# v2.net
KiCad netlist of a schematic drawn in EAGLE
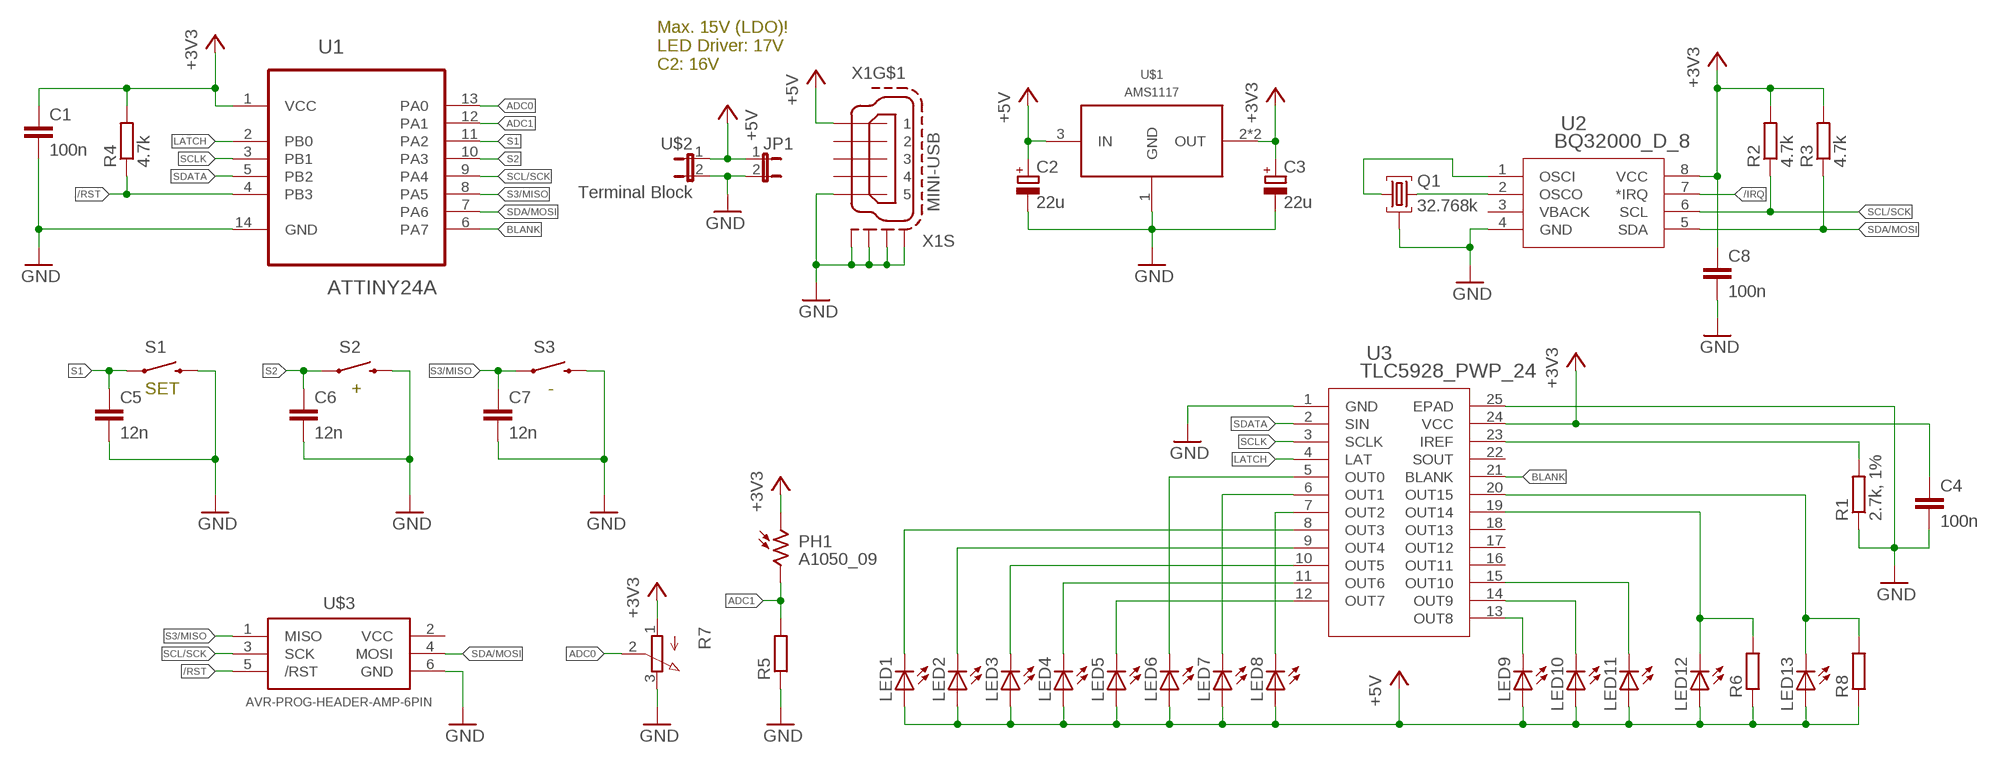
[diagram p0: schematic, sheet 1]
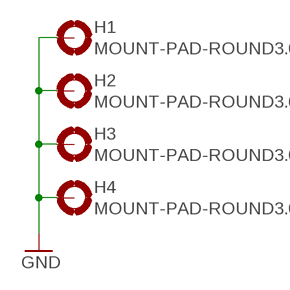
[diagram p1: schematic, sheet 2]

(export (version "E")
  (design (tool "Eeschema 10.0.6"))
  (components
    (comp (ref "H1")
      (value "MOUNT-PAD-ROUND3.0")
      (footprint "eagle-import:3,0-PAD")
      (libsource (lib "eagle-import") (part "MOUNT-PAD-ROUND3.0"))
    )
    (comp (ref "H2")
      (value "MOUNT-PAD-ROUND3.0")
      (footprint "eagle-import:3,0-PAD")
      (libsource (lib "eagle-import") (part "MOUNT-PAD-ROUND3.0"))
    )
    (comp (ref "H3")
      (value "MOUNT-PAD-ROUND3.0")
      (footprint "eagle-import:3,0-PAD")
      (libsource (lib "eagle-import") (part "MOUNT-PAD-ROUND3.0"))
    )
    (comp (ref "H4")
      (value "MOUNT-PAD-ROUND3.0")
      (footprint "eagle-import:3,0-PAD")
      (libsource (lib "eagle-import") (part "MOUNT-PAD-ROUND3.0"))
    )
    (comp (ref "C1")
      (value "100n")
      (footprint "eagle-import:C0603")
      (libsource (lib "eagle-import") (part "C-EUC0603"))
    )
    (comp (ref "C2")
      (value "22u")
      (footprint "eagle-import:153CLV-0505")
      (libsource (lib "eagle-import") (part "CPOL-EU153CLV-0505"))
    )
    (comp (ref "C3")
      (value "22u")
      (footprint "eagle-import:153CLV-0505")
      (libsource (lib "eagle-import") (part "CPOL-EU153CLV-0505"))
    )
    (comp (ref "C4")
      (value "100n")
      (footprint "eagle-import:C0603")
      (libsource (lib "eagle-import") (part "C-EUC0603"))
    )
    (comp (ref "C5")
      (value "12n")
      (footprint "eagle-import:C0603")
      (libsource (lib "eagle-import") (part "C-EUC0603"))
    )
    (comp (ref "C6")
      (value "12n")
      (footprint "eagle-import:C0603")
      (libsource (lib "eagle-import") (part "C-EUC0603"))
    )
    (comp (ref "C7")
      (value "12n")
      (footprint "eagle-import:C0603")
      (libsource (lib "eagle-import") (part "C-EUC0603"))
    )
    (comp (ref "C8")
      (value "100n")
      (footprint "eagle-import:C0603")
      (libsource (lib "eagle-import") (part "C-EUC0603"))
    )
    (comp (ref "JP1")
      (value "JP1E")
      (footprint "eagle-import:JP1")
      (libsource (lib "eagle-import") (part "JP1E"))
    )
    (comp (ref "LED1")
      (value "LEDCHIP-LED0603")
      (footprint "eagle-import:CHIP-LED0603")
      (libsource (lib "eagle-import") (part "LEDCHIP-LED0603"))
    )
    (comp (ref "LED2")
      (value "LEDCHIP-LED0603")
      (footprint "eagle-import:CHIP-LED0603")
      (libsource (lib "eagle-import") (part "LEDCHIP-LED0603"))
    )
    (comp (ref "LED3")
      (value "LEDCHIP-LED0603")
      (footprint "eagle-import:CHIP-LED0603")
      (libsource (lib "eagle-import") (part "LEDCHIP-LED0603"))
    )
    (comp (ref "LED4")
      (value "LEDCHIP-LED0603")
      (footprint "eagle-import:CHIP-LED0603")
      (libsource (lib "eagle-import") (part "LEDCHIP-LED0603"))
    )
    (comp (ref "LED5")
      (value "LEDCHIP-LED0603")
      (footprint "eagle-import:CHIP-LED0603")
      (libsource (lib "eagle-import") (part "LEDCHIP-LED0603"))
    )
    (comp (ref "LED6")
      (value "LEDCHIP-LED0603")
      (footprint "eagle-import:CHIP-LED0603")
      (libsource (lib "eagle-import") (part "LEDCHIP-LED0603"))
    )
    (comp (ref "LED7")
      (value "LEDCHIP-LED0603")
      (footprint "eagle-import:CHIP-LED0603")
      (libsource (lib "eagle-import") (part "LEDCHIP-LED0603"))
    )
    (comp (ref "LED8")
      (value "LEDCHIP-LED0603")
      (footprint "eagle-import:CHIP-LED0603")
      (libsource (lib "eagle-import") (part "LEDCHIP-LED0603"))
    )
    (comp (ref "LED9")
      (value "LEDCHIP-LED0603")
      (footprint "eagle-import:CHIP-LED0603")
      (libsource (lib "eagle-import") (part "LEDCHIP-LED0603"))
    )
    (comp (ref "LED10")
      (value "LEDCHIP-LED0603")
      (footprint "eagle-import:CHIP-LED0603")
      (libsource (lib "eagle-import") (part "LEDCHIP-LED0603"))
    )
    (comp (ref "LED11")
      (value "LEDCHIP-LED0603")
      (footprint "eagle-import:CHIP-LED0603")
      (libsource (lib "eagle-import") (part "LEDCHIP-LED0603"))
    )
    (comp (ref "LED12")
      (value "LEDCHIP-LED0603")
      (footprint "eagle-import:CHIP-LED0603")
      (libsource (lib "eagle-import") (part "LEDCHIP-LED0603"))
    )
    (comp (ref "LED13")
      (value "LEDCHIP-LED0603")
      (footprint "eagle-import:CHIP-LED0603")
      (libsource (lib "eagle-import") (part "LEDCHIP-LED0603"))
    )
    (comp (ref "PH1")
      (value "A1050_09")
      (footprint "eagle-import:T0-46-A10XX")
      (libsource (lib "eagle-import") (part "A1050_09"))
    )
    (comp (ref "Q1")
      (value "32.768k")
      (footprint "eagle-import:TC38")
      (libsource (lib "eagle-import") (part "CRYSTAL_TC38_SHIELD"))
    )
    (comp (ref "R1")
      (value "2.7k, 1%")
      (footprint "eagle-import:R1206")
      (libsource (lib "eagle-import") (part "R-EU_R1206"))
    )
    (comp (ref "R2")
      (value "4.7k")
      (footprint "eagle-import:R0603")
      (libsource (lib "eagle-import") (part "R-EU_R0603"))
    )
    (comp (ref "R3")
      (value "4.7k")
      (footprint "eagle-import:R0603")
      (libsource (lib "eagle-import") (part "R-EU_R0603"))
    )
    (comp (ref "R4")
      (value "4.7k")
      (footprint "eagle-import:R0603")
      (libsource (lib "eagle-import") (part "R-EU_R0603"))
    )
    (comp (ref "R5")
      (value "R-EU_R0603")
      (footprint "eagle-import:R0603")
      (libsource (lib "eagle-import") (part "R-EU_R0603"))
    )
    (comp (ref "R6")
      (value "R-EU_R0603")
      (footprint "eagle-import:R0603")
      (libsource (lib "eagle-import") (part "R-EU_R0603"))
    )
    (comp (ref "R7")
      (value "3RP/1610N")
      (footprint "eagle-import:3RP_1610N")
      (libsource (lib "eagle-import") (part "3RP/1610N"))
    )
    (comp (ref "R8")
      (value "R-EU_R0603")
      (footprint "eagle-import:R0603")
      (libsource (lib "eagle-import") (part "R-EU_R0603"))
    )
    (comp (ref "S1")
      (value "SWITCH-MOMENTARY-2PTH")
      (footprint "eagle-import:TACTILE-PTH")
      (libsource (lib "eagle-import") (part "SWITCH-MOMENTARY-2PTH"))
    )
    (comp (ref "S2")
      (value "SWITCH-MOMENTARY-2PTH")
      (footprint "eagle-import:TACTILE-PTH")
      (libsource (lib "eagle-import") (part "SWITCH-MOMENTARY-2PTH"))
    )
    (comp (ref "S3")
      (value "SWITCH-MOMENTARY-2PTH")
      (footprint "eagle-import:TACTILE-PTH")
      (libsource (lib "eagle-import") (part "SWITCH-MOMENTARY-2PTH"))
    )
    (comp (ref "U$1")
      (value "AMS1117")
      (footprint "eagle-import:DCY4")
      (libsource (lib "eagle-import") (part "AMS1117"))
    )
    (comp (ref "U$2")
      (value "Terminal Block")
      (footprint "eagle-import:BASTLI_SCREW_TERMINAL_SMALL")
      (libsource (lib "eagle-import") (part "BASTLI_SCREW_TERMINAL_SMALL"))
    )
    (comp (ref "U$3")
      (value "AVR-PROG-HEADER-AMP-6PIN")
      (footprint "eagle-import:AMP-TMM-1-0-06")
      (libsource (lib "eagle-import") (part "AVR-PROG-HEADER-AMP-6PIN"))
    )
    (comp (ref "U1")
      (value "ATTINY24A")
      (footprint "eagle-import:SOIC127P600X175-14N")
      (fields (field (name "MPN") "ATTINY24A-SSU"))
      (libsource (lib "eagle-import") (part "ATTINY24A-SSU"))
    )
    (comp (ref "U2")
      (value "BQ32000_D_8")
      (footprint "eagle-import:D8")
      (fields
        (field (name "GENERIC_PART_NUMBER") "BQ32000")
        (field (name "MANUFACTURER") "Texas Instruments")
      )
      (libsource (lib "eagle-import") (part "BQ32000_D_8"))
    )
    (comp (ref "U3")
      (value "TLC5928_PWP_24")
      (footprint "eagle-import:PWP24_4P87X2P4")
      (fields
        (field (name "GENERIC_PART_NUMBER") "TLC5928")
        (field (name "MANUFACTURER") "Texas Instruments")
        (field (name "MANUFACTURER_PART_NUMBER") "tlc5928_pwp_24")
      )
      (libsource (lib "eagle-import") (part "TLC5928_PWP_24"))
    )
    (comp (ref "X1")
      (value "MINI-USB")
      (footprint "eagle-import:32005-201")
      (libsource (lib "eagle-import") (part "MINI-USB-SCHIELD-32005-201"))
    )
  )
  (nets
    (net (code "1") (name "+3V3") (class "Default")
      (node (ref "C1") (pin "1") (pinfunction "1_1") (pintype "passive"))
      (node (ref "C3") (pin "+") (pinfunction "+_+") (pintype "passive"))
      (node (ref "C4") (pin "1") (pinfunction "1_1") (pintype "passive"))
      (node (ref "C8") (pin "1") (pinfunction "1_1") (pintype "passive"))
      (node (ref "PH1") (pin "1") (pinfunction "1_1") (pintype "passive"))
      (node (ref "R2") (pin "2") (pinfunction "2_2") (pintype "passive"))
      (node (ref "R3") (pin "2") (pinfunction "2_2") (pintype "passive"))
      (node (ref "R4") (pin "2") (pinfunction "2_2") (pintype "passive"))
      (node (ref "R7") (pin "1") (pinfunction "A_1") (pintype "passive"))
      (node (ref "U$1") (pin "2") (pinfunction "OUT_2") (pintype "power_in"))
      (node (ref "U$1") (pin "4") (pinfunction "OUT_4") (pintype "power_in"))
      (node (ref "U1") (pin "1") (pinfunction "VCC_1") (pintype "power_in"))
      (node (ref "U2") (pin "8") (pinfunction "VCC_8") (pintype "power_in"))
      (node (ref "U3") (pin "24") (pinfunction "VCC_24") (pintype "power_in"))
    )
    (net (code "2") (name "+5V") (class "Default")
      (node (ref "C2") (pin "+") (pinfunction "+_+") (pintype "passive"))
      (node (ref "JP1") (pin "1") (pinfunction "1_1") (pintype "passive"))
      (node (ref "LED1") (pin "A") (pinfunction "A_A") (pintype "passive"))
      (node (ref "LED10") (pin "A") (pinfunction "A_A") (pintype "passive"))
      (node (ref "LED11") (pin "A") (pinfunction "A_A") (pintype "passive"))
      (node (ref "LED12") (pin "A") (pinfunction "A_A") (pintype "passive"))
      (node (ref "LED13") (pin "A") (pinfunction "A_A") (pintype "passive"))
      (node (ref "LED2") (pin "A") (pinfunction "A_A") (pintype "passive"))
      (node (ref "LED3") (pin "A") (pinfunction "A_A") (pintype "passive"))
      (node (ref "LED4") (pin "A") (pinfunction "A_A") (pintype "passive"))
      (node (ref "LED5") (pin "A") (pinfunction "A_A") (pintype "passive"))
      (node (ref "LED6") (pin "A") (pinfunction "A_A") (pintype "passive"))
      (node (ref "LED7") (pin "A") (pinfunction "A_A") (pintype "passive"))
      (node (ref "LED8") (pin "A") (pinfunction "A_A") (pintype "passive"))
      (node (ref "LED9") (pin "A") (pinfunction "A_A") (pintype "passive"))
      (node (ref "R6") (pin "1") (pinfunction "1_1") (pintype "passive"))
      (node (ref "R8") (pin "1") (pinfunction "1_1") (pintype "passive"))
      (node (ref "U$1") (pin "3") (pinfunction "IN_3") (pintype "power_in"))
      (node (ref "U$2") (pin "1") (pinfunction "1_1") (pintype "passive"))
      (node (ref "X1") (pin "1") (pinfunction "1_1") (pintype "passive"))
    )
    (net (code "3") (name "ADC0") (class "Default")
      (node (ref "R7") (pin "2") (pinfunction "S_2") (pintype "passive"))
      (node (ref "U1") (pin "13") (pinfunction "PA0_13") (pintype "bidirectional"))
    )
    (net (code "4") (name "ADC1") (class "Default")
      (node (ref "PH1") (pin "2") (pinfunction "2_2") (pintype "passive"))
      (node (ref "R5") (pin "2") (pinfunction "2_2") (pintype "passive"))
      (node (ref "U1") (pin "12") (pinfunction "PA1_12") (pintype "bidirectional"))
    )
    (net (code "5") (name "BLANK") (class "Default")
      (node (ref "U1") (pin "6") (pinfunction "PA7_6") (pintype "bidirectional"))
      (node (ref "U3") (pin "21") (pinfunction "BLANK_21") (pintype "input"))
    )
    (net (code "6") (name "GND") (class "Default")
      (node (ref "C1") (pin "2") (pinfunction "2_2") (pintype "passive"))
      (node (ref "C2") (pin "-") (pinfunction "-_-") (pintype "passive"))
      (node (ref "C3") (pin "-") (pinfunction "-_-") (pintype "passive"))
      (node (ref "C4") (pin "2") (pinfunction "2_2") (pintype "passive"))
      (node (ref "C5") (pin "2") (pinfunction "2_2") (pintype "passive"))
      (node (ref "C6") (pin "2") (pinfunction "2_2") (pintype "passive"))
      (node (ref "C7") (pin "2") (pinfunction "2_2") (pintype "passive"))
      (node (ref "C8") (pin "2") (pinfunction "2_2") (pintype "passive"))
      (node (ref "H1") (pin "B3,0") (pinfunction "MOUNT_B3,0") (pintype "passive"))
      (node (ref "H2") (pin "B3,0") (pinfunction "MOUNT_B3,0") (pintype "passive"))
      (node (ref "H3") (pin "B3,0") (pinfunction "MOUNT_B3,0") (pintype "passive"))
      (node (ref "H4") (pin "B3,0") (pinfunction "MOUNT_B3,0") (pintype "passive"))
      (node (ref "JP1") (pin "2") (pinfunction "2_2") (pintype "passive"))
      (node (ref "Q1") (pin "1") (pinfunction "2_1") (pintype "passive"))
      (node (ref "R1") (pin "1") (pinfunction "1_1") (pintype "passive"))
      (node (ref "R5") (pin "1") (pinfunction "1_1") (pintype "passive"))
      (node (ref "R7") (pin "3") (pinfunction "E_3") (pintype "passive"))
      (node (ref "S1") (pin "3") (pinfunction "2_3") (pintype "passive"))
      (node (ref "S2") (pin "3") (pinfunction "2_3") (pintype "passive"))
      (node (ref "S3") (pin "3") (pinfunction "2_3") (pintype "passive"))
      (node (ref "U$1") (pin "1") (pinfunction "GND_1") (pintype "input"))
      (node (ref "U$2") (pin "2") (pinfunction "2_2") (pintype "passive"))
      (node (ref "U$3") (pin "6") (pinfunction "GND_6") (pintype "bidirectional"))
      (node (ref "U1") (pin "14") (pinfunction "GND_14") (pintype "power_in"))
      (node (ref "U2") (pin "4") (pinfunction "GND_4") (pintype "power_in"))
      (node (ref "U3") (pin "1") (pinfunction "GND_1") (pintype "power_in"))
      (node (ref "U3") (pin "25") (pinfunction "EPAD_25") (pintype "passive"))
      (node (ref "X1") (pin "5") (pinfunction "5_5") (pintype "passive"))
      (node (ref "X1") (pin "M1") (pinfunction "S1_M1") (pintype "passive"))
      (node (ref "X1") (pin "M2") (pinfunction "S2_M2") (pintype "passive"))
      (node (ref "X1") (pin "M3") (pinfunction "S3_M3") (pintype "passive"))
      (node (ref "X1") (pin "M4") (pinfunction "S4_M4") (pintype "passive"))
    )
    (net (code "7") (name "LATCH") (class "Default")
      (node (ref "U1") (pin "2") (pinfunction "PB0_2") (pintype "bidirectional"))
      (node (ref "U3") (pin "4") (pinfunction "LAT_4") (pintype "input"))
    )
    (net (code "8") (name "Net-(Q1-1)") (class "Default")
      (node (ref "Q1") (pin "2") (pinfunction "1_2") (pintype "passive"))
      (node (ref "U2") (pin "1") (pinfunction "OSCI_1") (pintype "input"))
    )
    (net (code "9") (name "Net-(U2-OSCO)") (class "Default")
      (node (ref "Q1") (pin "3") (pinfunction "3_3") (pintype "passive"))
      (node (ref "U2") (pin "2") (pinfunction "OSCO_2") (pintype "passive"))
    )
    (net (code "10") (name "Net-(U3-IREF)") (class "Default")
      (node (ref "R1") (pin "2") (pinfunction "2_2") (pintype "passive"))
      (node (ref "U3") (pin "23") (pinfunction "IREF_23") (pintype "bidirectional"))
    )
    (net (code "11") (name "Net-(U3-OUT0)") (class "Default")
      (node (ref "LED6") (pin "C") (pinfunction "C_C") (pintype "passive"))
      (node (ref "U3") (pin "5") (pinfunction "OUT0_5") (pintype "output"))
    )
    (net (code "12") (name "Net-(U3-OUT1)") (class "Default")
      (node (ref "LED7") (pin "C") (pinfunction "C_C") (pintype "passive"))
      (node (ref "U3") (pin "6") (pinfunction "OUT1_6") (pintype "output"))
    )
    (net (code "13") (name "Net-(U3-OUT2)") (class "Default")
      (node (ref "LED8") (pin "C") (pinfunction "C_C") (pintype "passive"))
      (node (ref "U3") (pin "7") (pinfunction "OUT2_7") (pintype "output"))
    )
    (net (code "14") (name "Net-(U3-OUT3)") (class "Default")
      (node (ref "LED1") (pin "C") (pinfunction "C_C") (pintype "passive"))
      (node (ref "U3") (pin "8") (pinfunction "OUT3_8") (pintype "output"))
    )
    (net (code "15") (name "Net-(U3-OUT4)") (class "Default")
      (node (ref "LED2") (pin "C") (pinfunction "C_C") (pintype "passive"))
      (node (ref "U3") (pin "9") (pinfunction "OUT4_9") (pintype "output"))
    )
    (net (code "16") (name "Net-(U3-OUT5)") (class "Default")
      (node (ref "LED3") (pin "C") (pinfunction "C_C") (pintype "passive"))
      (node (ref "U3") (pin "10") (pinfunction "OUT5_10") (pintype "output"))
    )
    (net (code "17") (name "Net-(U3-OUT6)") (class "Default")
      (node (ref "LED4") (pin "C") (pinfunction "C_C") (pintype "passive"))
      (node (ref "U3") (pin "11") (pinfunction "OUT6_11") (pintype "output"))
    )
    (net (code "18") (name "Net-(U3-OUT7)") (class "Default")
      (node (ref "LED5") (pin "C") (pinfunction "C_C") (pintype "passive"))
      (node (ref "U3") (pin "12") (pinfunction "OUT7_12") (pintype "output"))
    )
    (net (code "19") (name "Net-(U3-OUT8)") (class "Default")
      (node (ref "LED9") (pin "C") (pinfunction "C_C") (pintype "passive"))
      (node (ref "U3") (pin "13") (pinfunction "OUT8_13") (pintype "output"))
    )
    (net (code "20") (name "Net-(U3-OUT9)") (class "Default")
      (node (ref "LED10") (pin "C") (pinfunction "C_C") (pintype "passive"))
      (node (ref "U3") (pin "14") (pinfunction "OUT9_14") (pintype "output"))
    )
    (net (code "21") (name "Net-(U3-OUT10)") (class "Default")
      (node (ref "LED11") (pin "C") (pinfunction "C_C") (pintype "passive"))
      (node (ref "U3") (pin "15") (pinfunction "OUT10_15") (pintype "output"))
    )
    (net (code "22") (name "Net-(U3-OUT14)") (class "Default")
      (node (ref "LED12") (pin "C") (pinfunction "C_C") (pintype "passive"))
      (node (ref "R6") (pin "2") (pinfunction "2_2") (pintype "passive"))
      (node (ref "U3") (pin "19") (pinfunction "OUT14_19") (pintype "output"))
    )
    (net (code "23") (name "Net-(U3-OUT15)") (class "Default")
      (node (ref "LED13") (pin "C") (pinfunction "C_C") (pintype "passive"))
      (node (ref "R8") (pin "2") (pinfunction "2_2") (pintype "passive"))
      (node (ref "U3") (pin "20") (pinfunction "OUT15_20") (pintype "output"))
    )
    (net (code "24") (name "S1") (class "Default")
      (node (ref "C5") (pin "1") (pinfunction "1_1") (pintype "passive"))
      (node (ref "S1") (pin "1") (pinfunction "1_1") (pintype "passive"))
      (node (ref "U1") (pin "11") (pinfunction "PA2_11") (pintype "bidirectional"))
    )
    (net (code "25") (name "S2") (class "Default")
      (node (ref "C6") (pin "1") (pinfunction "1_1") (pintype "passive"))
      (node (ref "S2") (pin "1") (pinfunction "1_1") (pintype "passive"))
      (node (ref "U1") (pin "10") (pinfunction "PA3_10") (pintype "bidirectional"))
    )
    (net (code "26") (name "S3{slash}MISO") (class "Default")
      (node (ref "C7") (pin "1") (pinfunction "1_1") (pintype "passive"))
      (node (ref "S3") (pin "1") (pinfunction "1_1") (pintype "passive"))
      (node (ref "U$3") (pin "1") (pinfunction "MISO_1") (pintype "bidirectional"))
      (node (ref "U1") (pin "8") (pinfunction "PA5_8") (pintype "bidirectional"))
    )
    (net (code "27") (name "SCLK") (class "Default")
      (node (ref "U1") (pin "3") (pinfunction "PB1_3") (pintype "bidirectional"))
      (node (ref "U3") (pin "3") (pinfunction "SCLK_3") (pintype "input"))
    )
    (net (code "28") (name "SCL{slash}SCK") (class "Default")
      (node (ref "R2") (pin "1") (pinfunction "1_1") (pintype "passive"))
      (node (ref "U$3") (pin "3") (pinfunction "SCK_3") (pintype "bidirectional"))
      (node (ref "U1") (pin "9") (pinfunction "PA4_9") (pintype "bidirectional"))
      (node (ref "U2") (pin "6") (pinfunction "SCL_6") (pintype "input"))
    )
    (net (code "29") (name "SDATA") (class "Default")
      (node (ref "U1") (pin "5") (pinfunction "PB2_5") (pintype "bidirectional"))
      (node (ref "U3") (pin "2") (pinfunction "SIN_2") (pintype "input"))
    )
    (net (code "30") (name "SDA{slash}MOSI") (class "Default")
      (node (ref "R3") (pin "1") (pinfunction "1_1") (pintype "passive"))
      (node (ref "U$3") (pin "4") (pinfunction "MOSI_4") (pintype "bidirectional"))
      (node (ref "U1") (pin "7") (pinfunction "PA6_7") (pintype "bidirectional"))
      (node (ref "U2") (pin "5") (pinfunction "SDA_5") (pintype "bidirectional"))
    )
    (net (code "31") (name "VBACK") (class "Default")
      (node (ref "U2") (pin "3") (pinfunction "VBACK_3") (pintype "power_in"))
    )
    (net (code "32") (name "unconnected-(U$3-VCC-Pad2)") (class "Default")
      (node (ref "U$3") (pin "2") (pinfunction "VCC_2") (pintype "bidirectional"))
    )
    (net (code "33") (name "unconnected-(U3-OUT11-Pad16)") (class "Default")
      (node (ref "U3") (pin "16") (pinfunction "OUT11_16") (pintype "output"))
    )
    (net (code "34") (name "unconnected-(U3-OUT12-Pad17)") (class "Default")
      (node (ref "U3") (pin "17") (pinfunction "OUT12_17") (pintype "output"))
    )
    (net (code "35") (name "unconnected-(U3-OUT13-Pad18)") (class "Default")
      (node (ref "U3") (pin "18") (pinfunction "OUT13_18") (pintype "output"))
    )
    (net (code "36") (name "unconnected-(U3-SOUT-Pad22)") (class "Default")
      (node (ref "U3") (pin "22") (pinfunction "SOUT_22") (pintype "output"))
    )
    (net (code "37") (name "unconnected-(X1-Pad2)") (class "Default")
      (node (ref "X1") (pin "2") (pinfunction "2_2") (pintype "passive"))
    )
    (net (code "38") (name "unconnected-(X1-Pad3)") (class "Default")
      (node (ref "X1") (pin "3") (pinfunction "3_3") (pintype "passive"))
    )
    (net (code "39") (name "unconnected-(X1-Pad4)") (class "Default")
      (node (ref "X1") (pin "4") (pinfunction "4_4") (pintype "passive"))
    )
    (net (code "40") (name "{slash}IRQ") (class "Default")
      (node (ref "U2") (pin "7") (pinfunction "*IRQ_7") (pintype "passive"))
    )
    (net (code "41") (name "{slash}RST") (class "Default")
      (node (ref "R4") (pin "1") (pinfunction "1_1") (pintype "passive"))
      (node (ref "U$3") (pin "5") (pinfunction "/RST_5") (pintype "bidirectional"))
      (node (ref "U1") (pin "4") (pinfunction "PB3_4") (pintype "bidirectional"))
    )
  )
)
